# int_grateur.net
KiCad netlist of a schematic drawn in Altium Designer
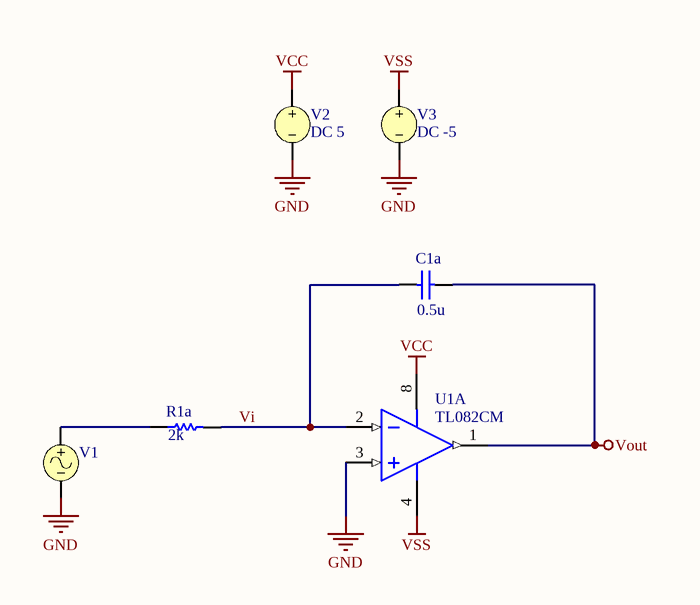
[diagram p0: intégrateur.SchDoc]

(export (version "E")
  (design (tool "Eeschema 10.0.6"))
  (components
    (comp (ref "C1a")
      (value "0.5u")
      (footprint "RAD-0.3")
      (description "Capacitor")
      (fields (field (name "Comment") "Cap") (field (name "PUBLISHER") "Altium Limited"))
      (libsource (lib "Miscellaneous Devices") (part "Cap"))
    )
    (comp (ref "R1a")
      (value "2k")
      (footprint "AXIAL-0.3")
      (description "Resistor")
      (fields (field (name "Comment") "Res1") (field (name "PUBLISHER") "Altium Limited"))
      (libsource (lib "Miscellaneous Devices") (part "Res1"))
    )
    (comp (ref "U1")
      (value "TL082CM")
      (footprint "M08A_N")
      (description "Wide Bandwidth Dual JFET Input Operational Amplifier, 8-pin Narrow SOIC")
      (fields
        (field (name "MANUFACTURER") "National Semiconductor")
        (field (name "PUBLISHER") "Altium Limited")
      )
      (libsource (lib "NSC Amplifier") (part "TL082CM"))
    )
    (comp (ref "V1")
      (value "PULSE(-1 1 0 1n 1n 0.05 0.1 0)")
      (description "Sinusoidal Voltage Source")
      (fields (field (name "PUBLISHER") "Altium Limited"))
      (libsource (lib "Simulation Sources") (part "VSIN"))
    )
    (comp (ref "V2")
      (value "DC 5")
      (description "Voltage Source")
      (fields (field (name "PUBLISHER") "Altium Limited"))
      (libsource (lib "Simulation Sources") (part "VSRC"))
    )
    (comp (ref "V3")
      (value "DC -5")
      (description "Voltage Source")
      (fields (field (name "PUBLISHER") "Altium Limited"))
      (libsource (lib "Simulation Sources") (part "VSRC"))
    )
  )
  (nets
    (net (code "2") (name "/Vi") (class "Default")
      (node (ref "C1a") (pin "1") (pinfunction "1_1") (pintype "passive"))
      (node (ref "R1a") (pin "2") (pinfunction "2_2") (pintype "passive"))
      (node (ref "U1") (pin "2") (pinfunction "INA-_2") (pintype "input"))
    )
    (net (code "3") (name "GND") (class "Default")
      (node (ref "U1") (pin "3") (pinfunction "INA+_3") (pintype "input"))
      (node (ref "V1") (pin "2") (pinfunction "2_2") (pintype "passive"))
      (node (ref "V2") (pin "2") (pinfunction "2_2") (pintype "passive"))
      (node (ref "V3") (pin "2") (pinfunction "2_2") (pintype "passive"))
    )
    (net (code "4") (name "Net-(R1a-Pad1)") (class "Default")
      (node (ref "R1a") (pin "1") (pinfunction "1_1") (pintype "passive"))
      (node (ref "V1") (pin "1") (pinfunction "1_1") (pintype "passive"))
    )
    (net (code "5") (name "VCC") (class "Default")
      (node (ref "U1") (pin "8") (pinfunction "V+_8") (pintype "power_in"))
      (node (ref "V2") (pin "1") (pinfunction "1_1") (pintype "passive"))
    )
    (net (code "6") (name "VSS") (class "Default")
      (node (ref "U1") (pin "4") (pinfunction "V-_4") (pintype "power_in"))
      (node (ref "V3") (pin "1") (pinfunction "1_1") (pintype "passive"))
    )
    (net (code "7") (name "Vout") (class "Default")
      (node (ref "C1a") (pin "2") (pinfunction "2_2") (pintype "passive"))
      (node (ref "U1") (pin "1") (pinfunction "OUTA_1") (pintype "output"))
    )
  )
)
